# LM399_Test_board.net
KiCad netlist of a schematic drawn in Altium Designer
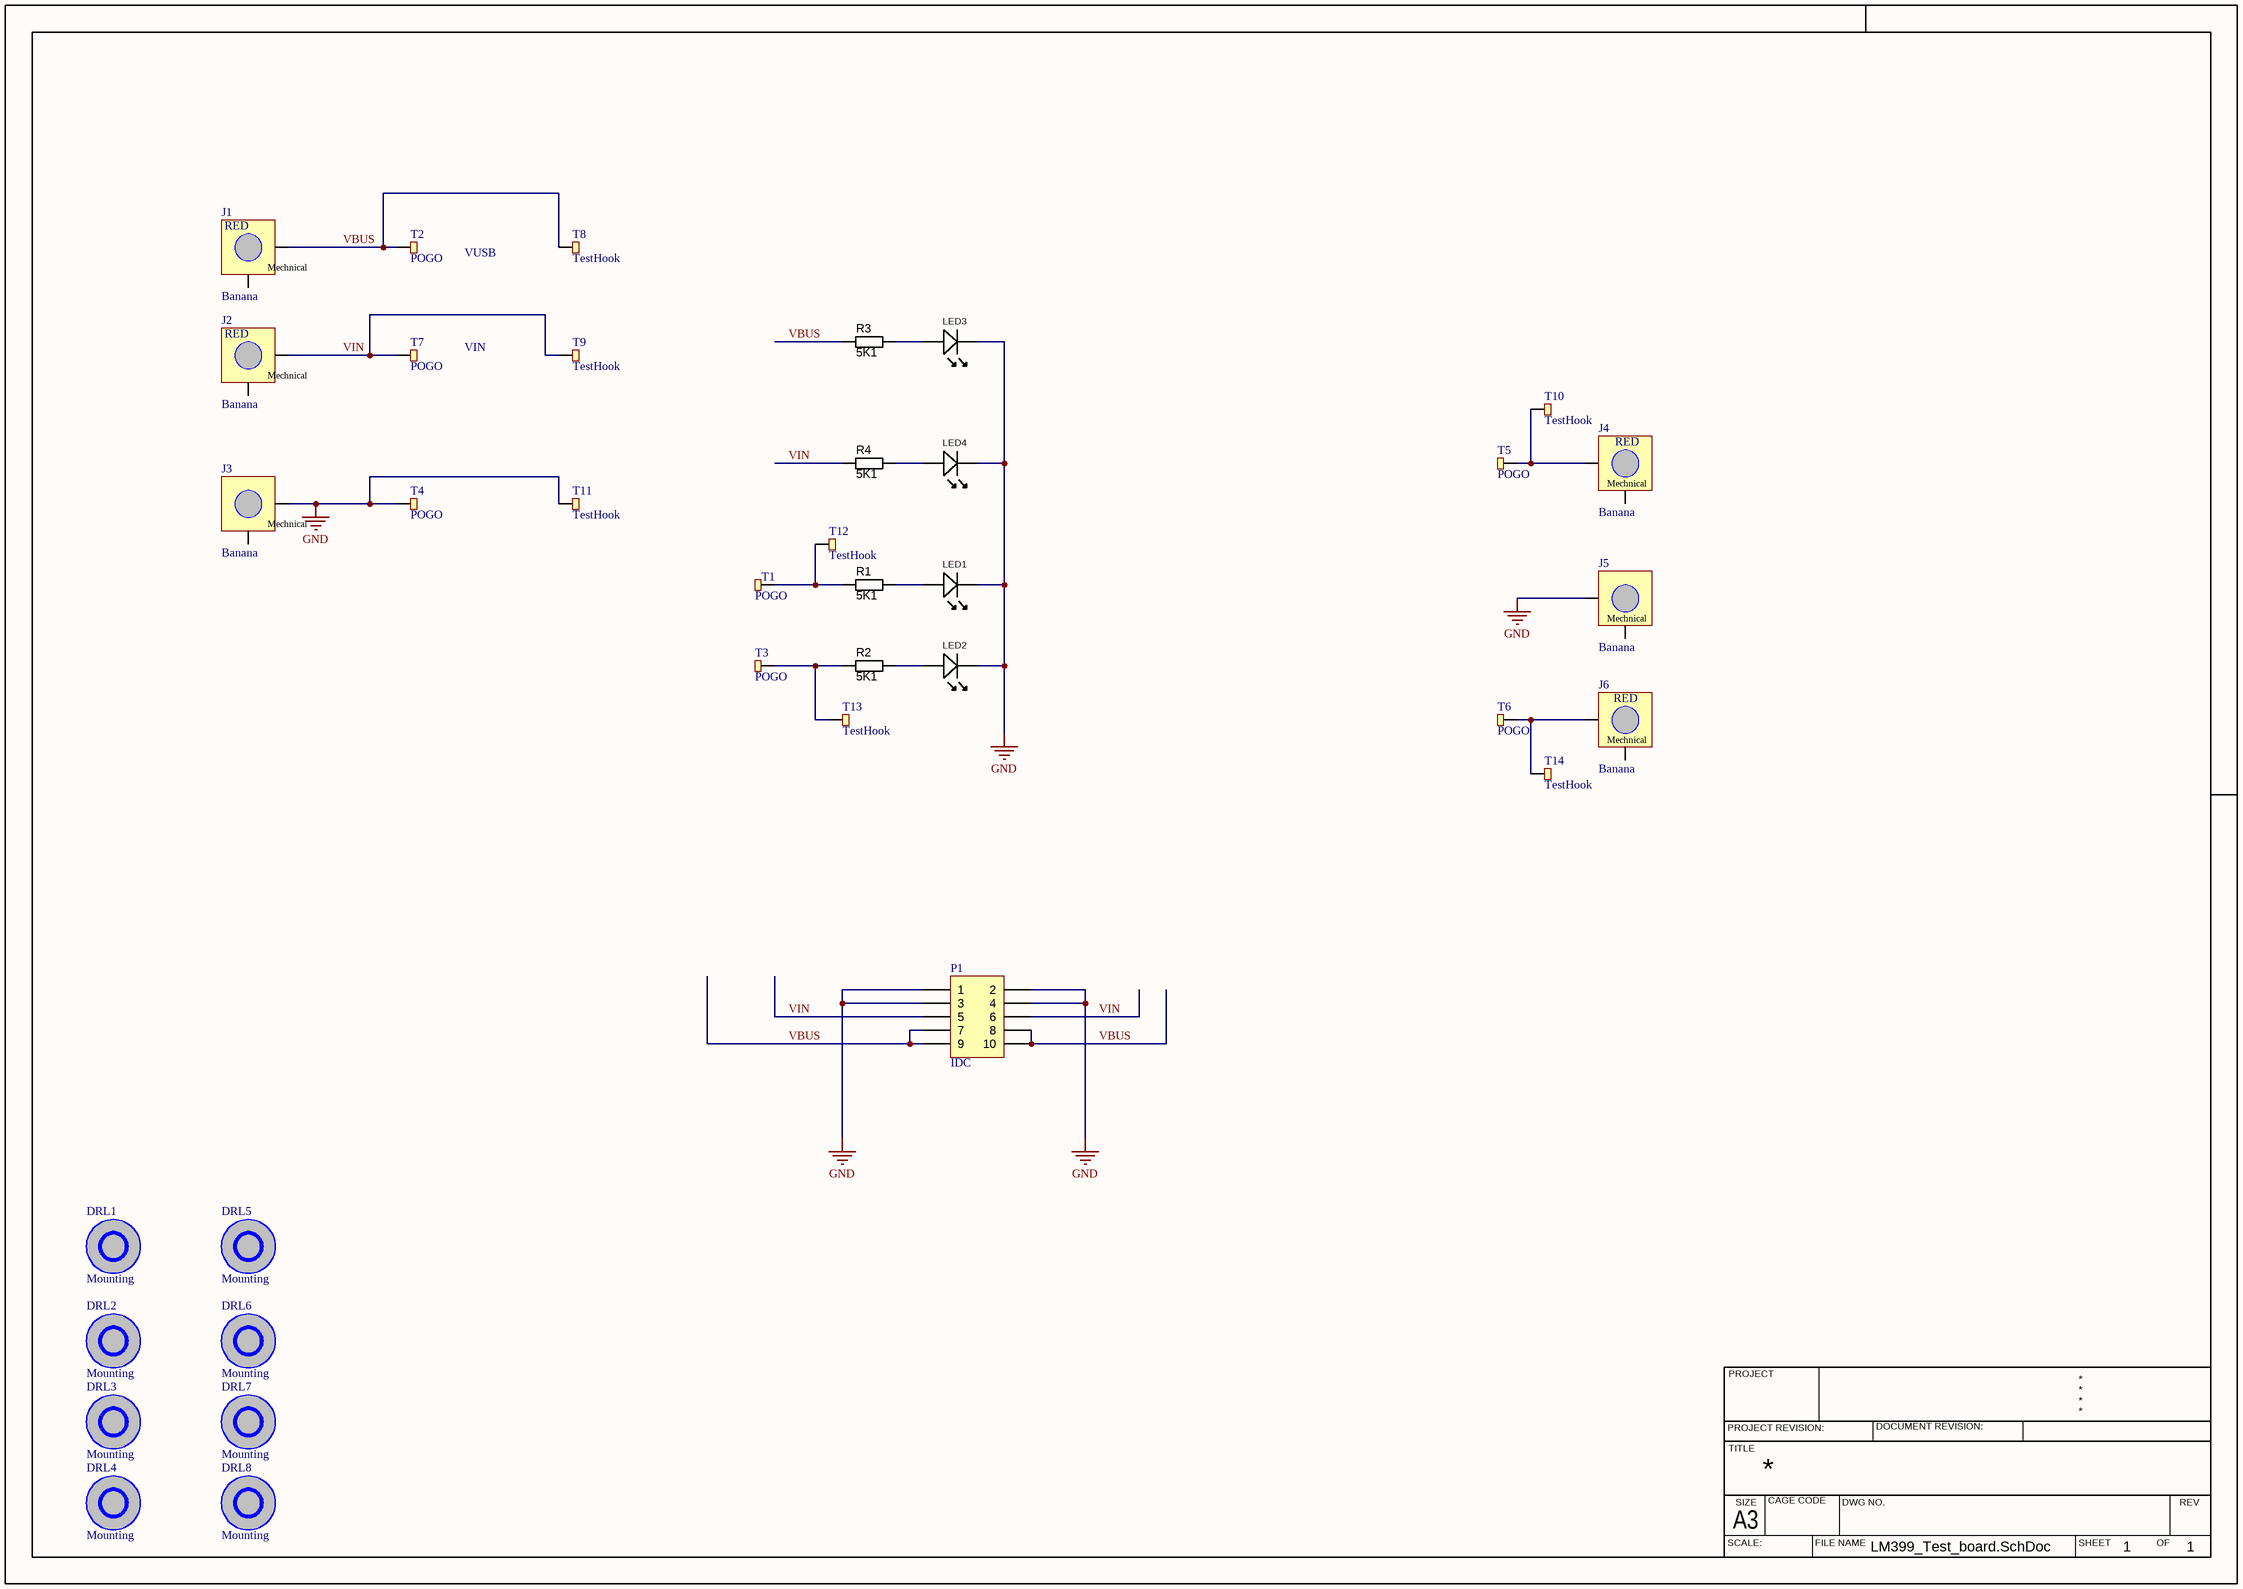
[diagram p0: LM399_Test_board.SchDoc]

(export (version "E")
  (design (tool "Eeschema 10.0.6"))
  (components
    (comp (ref "DRL1")
      (value "Mounting")
      (footprint "NO_COPPER_NOMASK_2m75_6m2")
      (description "Mounting Hole")
      (libsource (lib "cvlib") (part "Mountinghole"))
    )
    (comp (ref "DRL2")
      (value "Mounting")
      (footprint "NO_COPPER_NOMASK_2m75_6m2")
      (description "Mounting Hole")
      (libsource (lib "cvlib") (part "Mountinghole"))
    )
    (comp (ref "DRL3")
      (value "Mounting")
      (footprint "NO_COPPER_NOMASK_2m75_6m2")
      (description "Mounting Hole")
      (libsource (lib "cvlib") (part "Mountinghole"))
    )
    (comp (ref "DRL4")
      (value "Mounting")
      (footprint "NO_COPPER_NOMASK_2m75_6m2")
      (description "Mounting Hole")
      (libsource (lib "cvlib") (part "Mountinghole"))
    )
    (comp (ref "DRL5")
      (value "Mounting")
      (footprint "NO_COPPER_NOMASK_2m75_6m2")
      (description "Mounting Hole")
      (libsource (lib "cvlib") (part "Mountinghole"))
    )
    (comp (ref "DRL6")
      (value "Mounting")
      (footprint "NO_COPPER_NOMASK_2m75_6m2")
      (description "Mounting Hole")
      (libsource (lib "cvlib") (part "Mountinghole"))
    )
    (comp (ref "DRL7")
      (value "Mounting")
      (footprint "NO_COPPER_NOMASK_2m75_6m2")
      (description "Mounting Hole")
      (libsource (lib "cvlib") (part "Mountinghole"))
    )
    (comp (ref "DRL8")
      (value "Mounting")
      (footprint "NO_COPPER_NOMASK_2m75_6m2")
      (description "Mounting Hole")
      (libsource (lib "cvlib") (part "Mountinghole"))
    )
    (comp (ref "J1")
      (value "Banana")
      (footprint "Banana_66.9040-22_RED")
      (libsource (lib "cvlib") (part "Banana"))
    )
    (comp (ref "J2")
      (value "Banana")
      (footprint "Banana_66.9040-22_RED")
      (libsource (lib "cvlib") (part "Banana"))
    )
    (comp (ref "J3")
      (value "Banana")
      (footprint "Banana_66.9040-21_BLACK")
      (libsource (lib "cvlib") (part "Banana"))
    )
    (comp (ref "J4")
      (value "Banana")
      (footprint "Banana_66.9040-22_RED")
      (libsource (lib "") (part "Banana_1"))
    )
    (comp (ref "J5")
      (value "Banana")
      (footprint "Banana_66.9040-21_BLACK")
      (libsource (lib "") (part "Banana_1"))
    )
    (comp (ref "J6")
      (value "Banana")
      (footprint "Banana_66.9040-22_RED")
      (libsource (lib "") (part "Banana_1"))
    )
    (comp (ref "LED1")
      (value "~")
      (footprint "LED-0805-K")
      (description "LED, 0805 SMD, Green")
      (libsource (lib "PBL - Light Sources") (part "LED_SMD_Green_0805"))
    )
    (comp (ref "LED2")
      (value "~")
      (footprint "LED-0805-K")
      (description "LED, 0805 SMD, Green")
      (libsource (lib "PBL - Light Sources") (part "LED_SMD_Green_0805"))
    )
    (comp (ref "LED3")
      (value "~")
      (footprint "LED-0805-K")
      (description "LED, 0805 SMD, Green")
      (libsource (lib "PBL - Light Sources") (part "LED_SMD_Green_0805"))
    )
    (comp (ref "LED4")
      (value "~")
      (footprint "LED-0805-K")
      (description "LED, 0805 SMD, Green")
      (libsource (lib "PBL - Light Sources") (part "LED_SMD_Green_0805"))
    )
    (comp (ref "P1")
      (value "IDC")
      (footprint "HDR2X5")
      (description "Header, 5-Pin, Dual row")
      (fields (field (name "PART") "69830010LF") (field (name "PUBLISHER") "Altium Limited"))
      (libsource (lib "Miscellaneous Connectors") (part "Header 5X2"))
    )
    (comp (ref "R1")
      (value "5K1")
      (footprint "RESC1608N")
      (description "Resistor, SMD chip")
      (fields (field (name "TOLERANCE") "±5%") (field (name "Comment") "RES_NL_0603"))
      (libsource (lib "PBL - Resistors") (part "RES_NL_0603"))
    )
    (comp (ref "R2")
      (value "5K1")
      (footprint "RESC1608N")
      (description "Resistor, SMD chip")
      (fields (field (name "TOLERANCE") "±5%") (field (name "Comment") "RES_NL_0603"))
      (libsource (lib "PBL - Resistors") (part "RES_NL_0603"))
    )
    (comp (ref "R3")
      (value "5K1")
      (footprint "RESC1608N")
      (description "Resistor, SMD chip")
      (fields (field (name "TOLERANCE") "±5%") (field (name "Comment") "RES_NL_0603"))
      (libsource (lib "PBL - Resistors") (part "RES_NL_0603"))
    )
    (comp (ref "R4")
      (value "5K1")
      (footprint "RESC1608N")
      (description "Resistor, SMD chip")
      (fields (field (name "TOLERANCE") "±5%") (field (name "Comment") "RES_NL_0603"))
      (libsource (lib "PBL - Resistors") (part "RES_NL_0603"))
    )
    (comp (ref "T1")
      (value "POGO")
      (footprint "POGO_0851-0-15-20-82-14-11-0")
      (libsource (lib "") (part "TestHook_1"))
    )
    (comp (ref "T2")
      (value "POGO")
      (footprint "POGO_0851-0-15-20-82-14-11-0")
      (libsource (lib "cvlib") (part "TestHook"))
    )
    (comp (ref "T3")
      (value "POGO")
      (footprint "POGO_0851-0-15-20-82-14-11-0")
      (libsource (lib "") (part "TestHook_1"))
    )
    (comp (ref "T4")
      (value "POGO")
      (footprint "POGO_0851-0-15-20-82-14-11-0")
      (libsource (lib "cvlib") (part "TestHook"))
    )
    (comp (ref "T5")
      (value "POGO")
      (footprint "POGO_0851-0-15-20-82-14-11-0")
      (libsource (lib "") (part "TestHook_1"))
    )
    (comp (ref "T6")
      (value "POGO")
      (footprint "POGO_0851-0-15-20-82-14-11-0")
      (libsource (lib "") (part "TestHook_1"))
    )
    (comp (ref "T7")
      (value "POGO")
      (footprint "POGO_0851-0-15-20-82-14-11-0")
      (libsource (lib "cvlib") (part "TestHook"))
    )
    (comp (ref "T8") (value "TestHook") (footprint "1502-x") (libsource (lib "cvlib") (part "TestHook")))
    (comp (ref "T9") (value "TestHook") (footprint "1502-x") (libsource (lib "cvlib") (part "TestHook")))
    (comp (ref "T10") (value "TestHook") (footprint "1502-x") (libsource (lib "cvlib") (part "TestHook")))
    (comp (ref "T11") (value "TestHook") (footprint "1502-x") (libsource (lib "cvlib") (part "TestHook")))
    (comp (ref "T12") (value "TestHook") (footprint "1502-x") (libsource (lib "cvlib") (part "TestHook")))
    (comp (ref "T13") (value "TestHook") (footprint "1502-x") (libsource (lib "cvlib") (part "TestHook")))
    (comp (ref "T14") (value "TestHook") (footprint "1502-x") (libsource (lib "cvlib") (part "TestHook")))
  )
  (nets
    (net (code "1") (name "/VBUS") (class "Default")
      (node (ref "J1") (pin "1") (pinfunction "1_1") (pintype "passive"))
      (node (ref "P1") (pin "10") (pinfunction "10_10") (pintype "passive"))
      (node (ref "P1") (pin "7") (pinfunction "7_7") (pintype "passive"))
      (node (ref "P1") (pin "8") (pinfunction "8_8") (pintype "passive"))
      (node (ref "P1") (pin "9") (pinfunction "9_9") (pintype "passive"))
      (node (ref "R3") (pin "1") (pinfunction "1_1") (pintype "passive"))
      (node (ref "T2") (pin "1") (pinfunction "TP_1") (pintype "power_in"))
      (node (ref "T8") (pin "1") (pinfunction "TP_1") (pintype "power_in"))
    )
    (net (code "2") (name "/VIN") (class "Default")
      (node (ref "J2") (pin "1") (pinfunction "1_1") (pintype "passive"))
      (node (ref "P1") (pin "5") (pinfunction "5_5") (pintype "passive"))
      (node (ref "P1") (pin "6") (pinfunction "6_6") (pintype "passive"))
      (node (ref "R4") (pin "1") (pinfunction "1_1") (pintype "passive"))
      (node (ref "T7") (pin "1") (pinfunction "TP_1") (pintype "power_in"))
      (node (ref "T9") (pin "1") (pinfunction "TP_1") (pintype "power_in"))
    )
    (net (code "3") (name "GND") (class "Default")
      (node (ref "J3") (pin "1") (pinfunction "1_1") (pintype "passive"))
      (node (ref "J5") (pin "1") (pinfunction "1_1") (pintype "passive"))
      (node (ref "LED1") (pin "K") (pinfunction "K_K") (pintype "passive"))
      (node (ref "LED2") (pin "K") (pinfunction "K_K") (pintype "passive"))
      (node (ref "LED3") (pin "K") (pinfunction "K_K") (pintype "passive"))
      (node (ref "LED4") (pin "K") (pinfunction "K_K") (pintype "passive"))
      (node (ref "P1") (pin "1") (pinfunction "1_1") (pintype "passive"))
      (node (ref "P1") (pin "2") (pinfunction "2_2") (pintype "passive"))
      (node (ref "P1") (pin "3") (pinfunction "3_3") (pintype "passive"))
      (node (ref "P1") (pin "4") (pinfunction "4_4") (pintype "passive"))
      (node (ref "T11") (pin "1") (pinfunction "TP_1") (pintype "power_in"))
      (node (ref "T4") (pin "1") (pinfunction "TP_1") (pintype "power_in"))
    )
    (net (code "4") (name "Net-(LED1-PadA)") (class "Default")
      (node (ref "LED1") (pin "A") (pinfunction "A_A") (pintype "passive"))
      (node (ref "R1") (pin "2") (pinfunction "2_2") (pintype "passive"))
    )
    (net (code "5") (name "Net-(LED2-PadA)") (class "Default")
      (node (ref "LED2") (pin "A") (pinfunction "A_A") (pintype "passive"))
      (node (ref "R2") (pin "2") (pinfunction "2_2") (pintype "passive"))
    )
    (net (code "6") (name "Net-(LED3-PadA)") (class "Default")
      (node (ref "LED3") (pin "A") (pinfunction "A_A") (pintype "passive"))
      (node (ref "R3") (pin "2") (pinfunction "2_2") (pintype "passive"))
    )
    (net (code "7") (name "Net-(LED4-PadA)") (class "Default")
      (node (ref "LED4") (pin "A") (pinfunction "A_A") (pintype "passive"))
      (node (ref "R4") (pin "2") (pinfunction "2_2") (pintype "passive"))
    )
    (net (code "8") (name "Net-(T1-TP)") (class "Default")
      (node (ref "R1") (pin "1") (pinfunction "1_1") (pintype "passive"))
      (node (ref "T1") (pin "1") (pinfunction "TP_1") (pintype "power_in"))
      (node (ref "T12") (pin "1") (pinfunction "TP_1") (pintype "power_in"))
    )
    (net (code "9") (name "Net-(T10-TP)") (class "Default")
      (node (ref "J4") (pin "1") (pinfunction "1_1") (pintype "passive"))
      (node (ref "T10") (pin "1") (pinfunction "TP_1") (pintype "power_in"))
      (node (ref "T5") (pin "1") (pinfunction "TP_1") (pintype "power_in"))
    )
    (net (code "10") (name "Net-(T13-TP)") (class "Default")
      (node (ref "R2") (pin "1") (pinfunction "1_1") (pintype "passive"))
      (node (ref "T13") (pin "1") (pinfunction "TP_1") (pintype "power_in"))
      (node (ref "T3") (pin "1") (pinfunction "TP_1") (pintype "power_in"))
    )
    (net (code "11") (name "Net-(T14-TP)") (class "Default")
      (node (ref "J6") (pin "1") (pinfunction "1_1") (pintype "passive"))
      (node (ref "T14") (pin "1") (pinfunction "TP_1") (pintype "power_in"))
      (node (ref "T6") (pin "1") (pinfunction "TP_1") (pintype "power_in"))
    )
    (net (code "12") (name "unconnected-(J1-Pad2)") (class "Default")
      (node (ref "J1") (pin "2") (pinfunction "2_2") (pintype "passive"))
    )
    (net (code "13") (name "unconnected-(J2-Pad2)") (class "Default")
      (node (ref "J2") (pin "2") (pinfunction "2_2") (pintype "passive"))
    )
    (net (code "14") (name "unconnected-(J3-Pad2)") (class "Default")
      (node (ref "J3") (pin "2") (pinfunction "2_2") (pintype "passive"))
    )
    (net (code "15") (name "unconnected-(J4-Pad2)") (class "Default")
      (node (ref "J4") (pin "2") (pinfunction "2_2") (pintype "passive"))
    )
    (net (code "16") (name "unconnected-(J5-Pad2)") (class "Default")
      (node (ref "J5") (pin "2") (pinfunction "2_2") (pintype "passive"))
    )
    (net (code "17") (name "unconnected-(J6-Pad2)") (class "Default")
      (node (ref "J6") (pin "2") (pinfunction "2_2") (pintype "passive"))
    )
  )
)
